# untitled.net
KiCad netlist of a schematic drawn in EAGLE
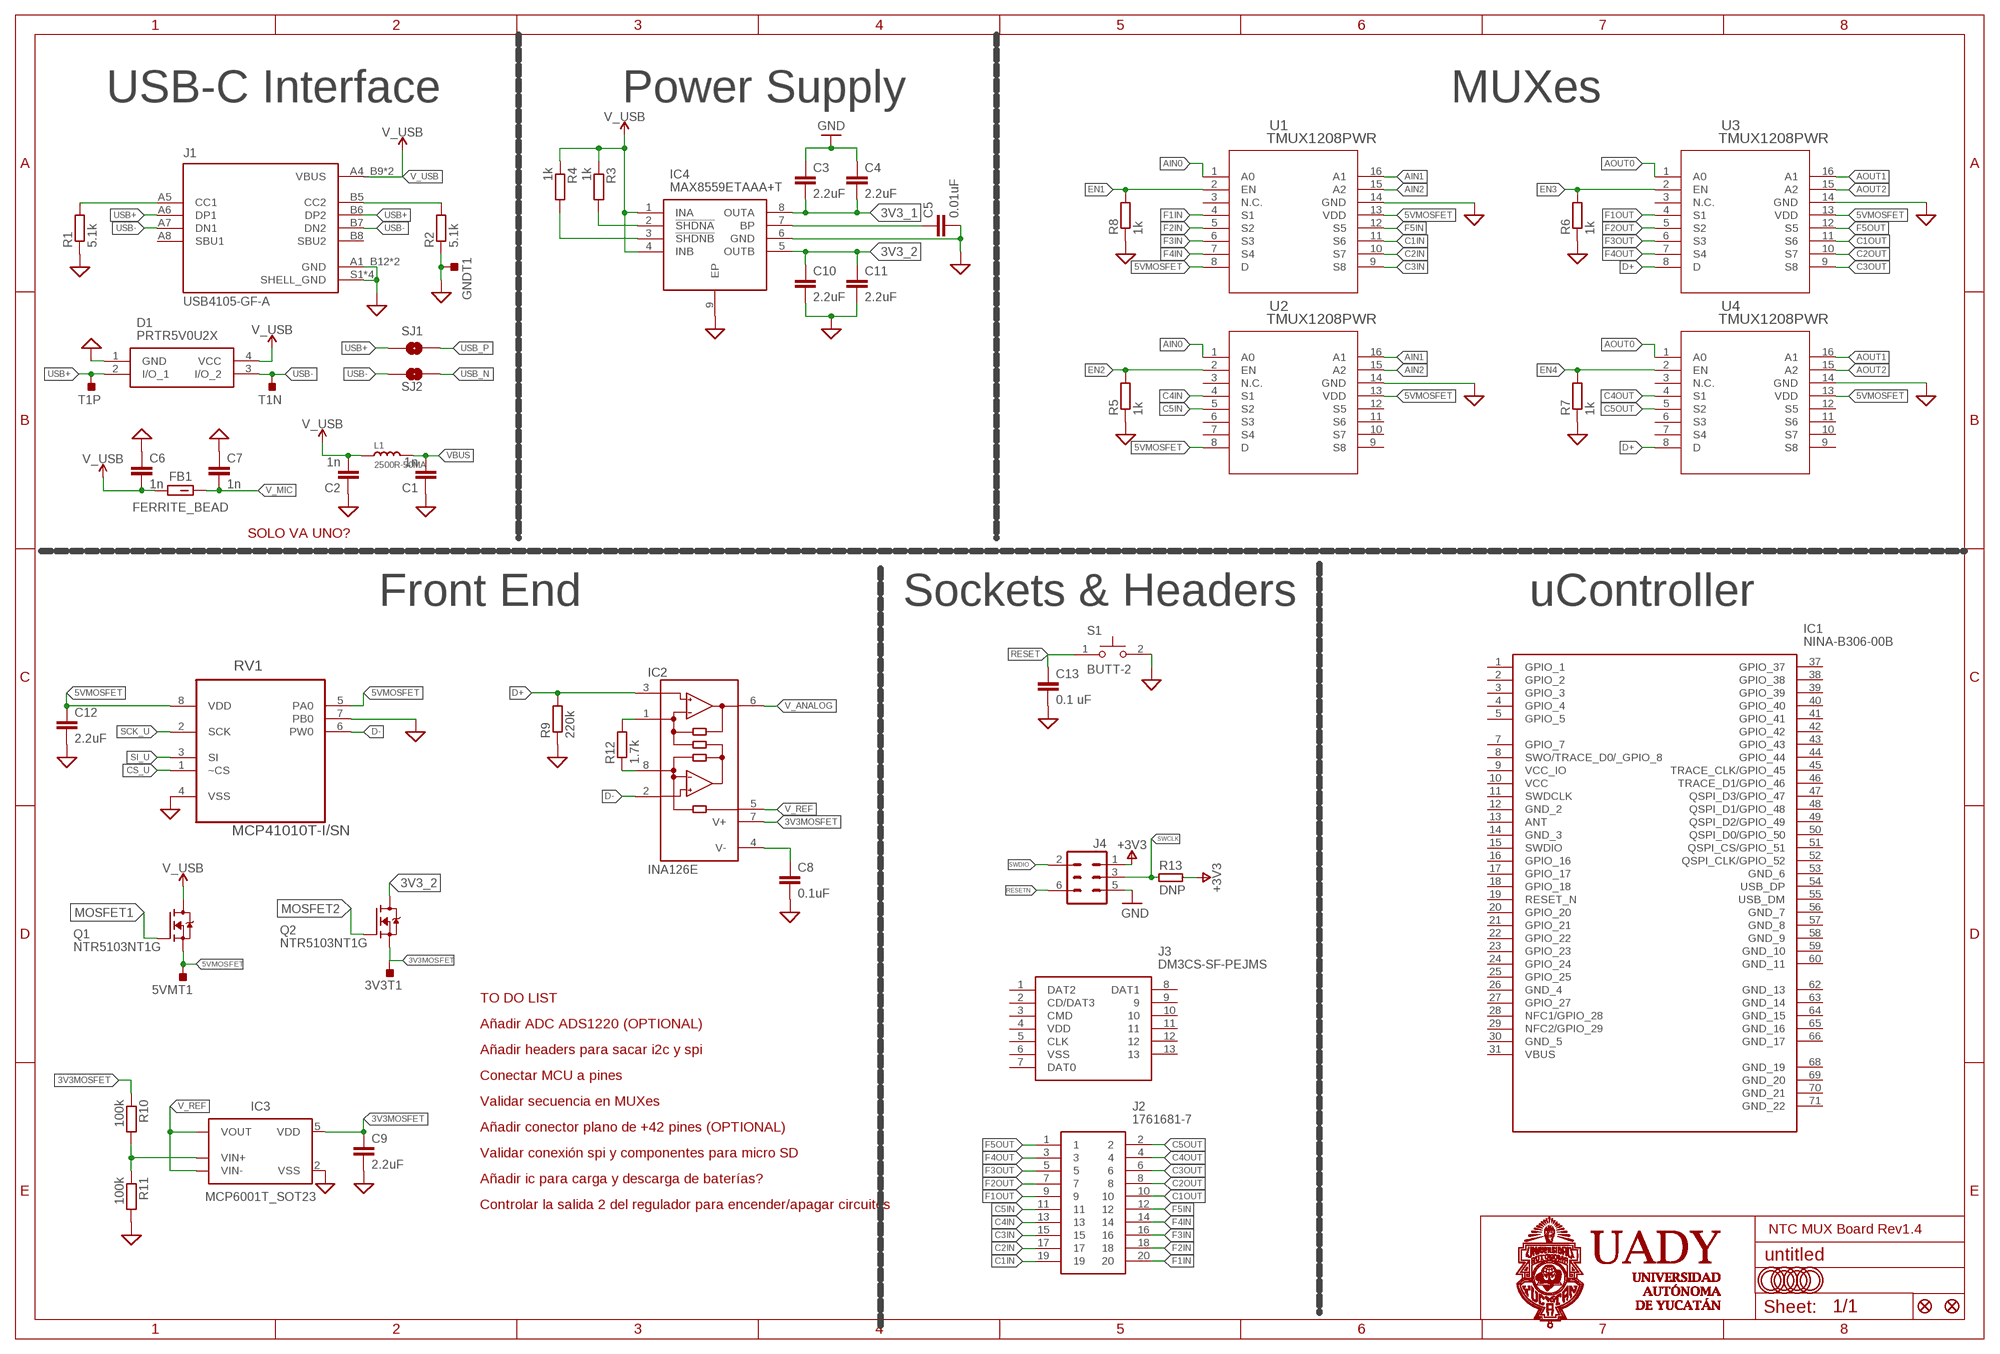
[diagram p0: schematic, sheet 1]

(export (version "E")
  (design (tool "Eeschema 10.0.6"))
  (components
    (comp (ref "3V3T1")
      (value "TESTPOINT_TPS-SMD-10SN")
      (footprint "eagle-import:TESTPOINT_SMD-10SN")
      (libsource (lib "eagle-import") (part "TESTPOINT_TPS-SMD-10SN"))
    )
    (comp (ref "5VMT1")
      (value "TESTPOINT_TPS-SMD-10SN")
      (footprint "eagle-import:TESTPOINT_SMD-10SN")
      (libsource (lib "eagle-import") (part "TESTPOINT_TPS-SMD-10SN"))
    )
    (comp (ref "C1")
      (value "1n")
      (footprint "eagle-import:C0603")
      (libsource (lib "eagle-import") (part "C-EUC0603"))
    )
    (comp (ref "C2")
      (value "1n")
      (footprint "eagle-import:C0603")
      (libsource (lib "eagle-import") (part "C-EUC0603"))
    )
    (comp (ref "C3")
      (value "2.2uF")
      (footprint "eagle-import:C0603")
      (libsource (lib "eagle-import") (part "C-EUC0603"))
    )
    (comp (ref "C4")
      (value "2.2uF")
      (footprint "eagle-import:C0603")
      (libsource (lib "eagle-import") (part "C-EUC0603"))
    )
    (comp (ref "C5")
      (value "0.01uF")
      (footprint "eagle-import:C0603")
      (libsource (lib "eagle-import") (part "C-EUC0603"))
    )
    (comp (ref "C6")
      (value "1n")
      (footprint "eagle-import:C0603")
      (libsource (lib "eagle-import") (part "C-EUC0603"))
    )
    (comp (ref "C7")
      (value "1n")
      (footprint "eagle-import:C0603")
      (libsource (lib "eagle-import") (part "C-EUC0603"))
    )
    (comp (ref "C8")
      (value "0.1uF")
      (footprint "eagle-import:C0603")
      (libsource (lib "eagle-import") (part "C-EUC0603"))
    )
    (comp (ref "C9")
      (value "2.2uF")
      (footprint "eagle-import:C0603")
      (libsource (lib "eagle-import") (part "C-EUC0603"))
    )
    (comp (ref "C10")
      (value "2.2uF")
      (footprint "eagle-import:C0603")
      (libsource (lib "eagle-import") (part "C-EUC0603"))
    )
    (comp (ref "C11")
      (value "2.2uF")
      (footprint "eagle-import:C0603")
      (libsource (lib "eagle-import") (part "C-EUC0603"))
    )
    (comp (ref "C12")
      (value "2.2uF")
      (footprint "eagle-import:C0603")
      (libsource (lib "eagle-import") (part "C-EUC0603"))
    )
    (comp (ref "C13")
      (value "0.1 uF")
      (footprint "eagle-import:C0603")
      (libsource (lib "eagle-import") (part "C-EUC0603"))
    )
    (comp (ref "D1")
      (value "PRTR5V0U2X")
      (footprint "eagle-import:PRTR5V0U2X")
      (libsource (lib "eagle-import") (part "PRTR5V0U2X"))
    )
    (comp (ref "FB1")
      (value "FERRITE_BEAD")
      (footprint "eagle-import:BEADC1608X95N")
      (libsource (lib "eagle-import") (part "FBCHIP-0603(1608-METRIC)"))
    )
    (comp (ref "FID1")
      (value "FIDUCIAL_1MM")
      (footprint "eagle-import:FIDUCIAL_1MM")
      (libsource (lib "eagle-import") (part "FIDUCIAL_1MM"))
    )
    (comp (ref "FID4")
      (value "FIDUCIAL_1MM")
      (footprint "eagle-import:FIDUCIAL_1MM")
      (libsource (lib "eagle-import") (part "FIDUCIAL_1MM"))
    )
    (comp (ref "GNDT1")
      (value "TESTPOINT_TPS-SMD-10SN")
      (footprint "eagle-import:TESTPOINT_SMD-10SN")
      (libsource (lib "eagle-import") (part "TESTPOINT_TPS-SMD-10SN"))
    )
    (comp (ref "IC1")
      (value "NINA-B306-00B")
      (footprint "eagle-import:NINAB30600B")
      (fields (field (name "MOUSER_PART_NUMBER") "377-NINA-B306-00B"))
      (libsource (lib "eagle-import") (part "NINA-B306-00B"))
    )
    (comp (ref "IC2")
      (value "INA126E")
      (footprint "eagle-import:MSOP08")
      (fields (field (name "MF") "Texas Instruments") (field (name "MP") "INA126"))
      (libsource (lib "eagle-import") (part "INA126E"))
    )
    (comp (ref "IC3")
      (value "MCP6001T_SOT23")
      (footprint "eagle-import:SOT95P280X145-5N")
      (fields (field (name "MANUFACTURER") "Microchip Technology") (field (name "MPN") "Generic"))
      (libsource (lib "eagle-import") (part "MCP6001T_SOT23"))
    )
    (comp (ref "IC4")
      (value "MAX8559ETAAA+T")
      (footprint "eagle-import:SON65P300X300X80-9N")
      (fields (field (name "MOUSER_PART_NUMBER") "700-MAX8559ETAAAT"))
      (libsource (lib "eagle-import") (part "MAX8559ETAAA+T"))
    )
    (comp (ref "J1")
      (value "USB4105-GF-A")
      (footprint "eagle-import:GCT_USB4105-GF-A")
      (fields (field (name "MF") "GCT"))
      (libsource (lib "eagle-import") (part "USB4105-GF-A"))
    )
    (comp (ref "J2")
      (value "1761681-7")
      (footprint "eagle-import:SHDR20W66P254_2X10_3302X883X92")
      (fields (field (name "MOUSER_PART_NUMBER") "571-1761681-7"))
      (libsource (lib "eagle-import") (part "1761681-7"))
    )
    (comp (ref "J3")
      (value "DM3CS-SF-PEJMS")
      (footprint "eagle-import:DM3CSSFPEJMS")
      (libsource (lib "eagle-import") (part "DM3CS-SF-PEJMS"))
    )
    (comp (ref "J4")
      (value "DNP")
      (footprint "eagle-import:2X03-TP1")
      (libsource (lib "eagle-import") (part "PINHD-2X03(NO4)"))
    )
    (comp (ref "L1")
      (value "2500R-50MA")
      (footprint "eagle-import:L0603")
      (libsource (lib "eagle-import") (part "SMD-FERRITE-BEAD-2500R-50MA(0603)"))
    )
    (comp (ref "Q1")
      (value "NTR5103NT1G")
      (footprint "eagle-import:SOT95P237X111-3N")
      (fields (field (name "MF") "ON Semiconductor"))
      (libsource (lib "eagle-import") (part "NTR5103NT1G"))
    )
    (comp (ref "Q2")
      (value "NTR5103NT1G")
      (footprint "eagle-import:SOT95P237X111-3N")
      (fields (field (name "MF") "ON Semiconductor"))
      (libsource (lib "eagle-import") (part "NTR5103NT1G"))
    )
    (comp (ref "R1")
      (value "5.1k")
      (footprint "eagle-import:R0603")
      (libsource (lib "eagle-import") (part "R-EU_R0603"))
    )
    (comp (ref "R2")
      (value "5.1k")
      (footprint "eagle-import:R0603")
      (libsource (lib "eagle-import") (part "R-EU_R0603"))
    )
    (comp (ref "R3")
      (value "1k")
      (footprint "eagle-import:R0603")
      (libsource (lib "eagle-import") (part "R-EU_R0603"))
    )
    (comp (ref "R4")
      (value "1k")
      (footprint "eagle-import:R0603")
      (libsource (lib "eagle-import") (part "R-EU_R0603"))
    )
    (comp (ref "R5")
      (value "1k")
      (footprint "eagle-import:R0603")
      (libsource (lib "eagle-import") (part "R-EU_R0603"))
    )
    (comp (ref "R6")
      (value "1k")
      (footprint "eagle-import:R0603")
      (libsource (lib "eagle-import") (part "R-EU_R0603"))
    )
    (comp (ref "R7")
      (value "1k")
      (footprint "eagle-import:R0603")
      (libsource (lib "eagle-import") (part "R-EU_R0603"))
    )
    (comp (ref "R8")
      (value "1k")
      (footprint "eagle-import:R0603")
      (libsource (lib "eagle-import") (part "R-EU_R0603"))
    )
    (comp (ref "R9")
      (value "220k")
      (footprint "eagle-import:R0603")
      (libsource (lib "eagle-import") (part "R-EU_R0603"))
    )
    (comp (ref "R10")
      (value "100k")
      (footprint "eagle-import:R0603")
      (libsource (lib "eagle-import") (part "R-EU_R0603"))
    )
    (comp (ref "R11")
      (value "100k")
      (footprint "eagle-import:R0603")
      (libsource (lib "eagle-import") (part "R-EU_R0603"))
    )
    (comp (ref "R12")
      (value "1.7k")
      (footprint "eagle-import:R0603")
      (libsource (lib "eagle-import") (part "R-EU_R0603"))
    )
    (comp (ref "R13")
      (value "DNP")
      (footprint "eagle-import:0402-1005X55N")
      (libsource (lib "eagle-import") (part "R-0402-DNP"))
    )
    (comp (ref "RV1")
      (value "MCP41010T-I/SN")
      (footprint "eagle-import:SOIC127P600X175-8N")
      (fields (field (name "MF") "Microchip Technology"))
      (libsource (lib "eagle-import") (part "MCP41010T-I/SN"))
    )
    (comp (ref "S1")
      (value "BUTT-2")
      (footprint "eagle-import:SW_BUTT-2")
      (fields (field (name "MF") "Gravitech"))
      (libsource (lib "eagle-import") (part "BUTT-2"))
    )
    (comp (ref "SJ1")
      (value "JUMPER-SMT_2_NO_NO-SILK")
      (footprint "eagle-import:SMT-JUMPER_2_NO_NO-SILK")
      (libsource (lib "eagle-import") (part "JUMPER-SMT_2_NO_NO-SILK"))
    )
    (comp (ref "SJ2")
      (value "JUMPER-SMT_2_NO_NO-SILK")
      (footprint "eagle-import:SMT-JUMPER_2_NO_NO-SILK")
      (libsource (lib "eagle-import") (part "JUMPER-SMT_2_NO_NO-SILK"))
    )
    (comp (ref "T1N")
      (value "TESTPOINT_TPS-SMD-10SN")
      (footprint "eagle-import:TESTPOINT_SMD-10SN")
      (libsource (lib "eagle-import") (part "TESTPOINT_TPS-SMD-10SN"))
    )
    (comp (ref "T1P")
      (value "TESTPOINT_TPS-SMD-10SN")
      (footprint "eagle-import:TESTPOINT_SMD-10SN")
      (libsource (lib "eagle-import") (part "TESTPOINT_TPS-SMD-10SN"))
    )
    (comp (ref "U$2")
      (value "MOUNTINGHOLE2.5")
      (footprint "eagle-import:MOUNTINGHOLE_2.5_PLATED")
      (libsource (lib "eagle-import") (part "MOUNTINGHOLE2.5"))
    )
    (comp (ref "U$3")
      (value "MOUNTINGHOLE2.5")
      (footprint "eagle-import:MOUNTINGHOLE_2.5_PLATED")
      (libsource (lib "eagle-import") (part "MOUNTINGHOLE2.5"))
    )
    (comp (ref "U$4")
      (value "MOUNTINGHOLE2.5")
      (footprint "eagle-import:MOUNTINGHOLE_2.5_PLATED")
      (libsource (lib "eagle-import") (part "MOUNTINGHOLE2.5"))
    )
    (comp (ref "U$24")
      (value "MOUNTINGHOLE2.5")
      (footprint "eagle-import:MOUNTINGHOLE_2.5_PLATED")
      (libsource (lib "eagle-import") (part "MOUNTINGHOLE2.5"))
    )
    (comp (ref "U1")
      (value "TMUX1208PWR")
      (footprint "eagle-import:PW_16_TEX")
      (fields (field (name "COPYRIGHT") "Copyright (C) 2022 Ultra Librarian. All rights reserved."))
      (libsource (lib "eagle-import") (part "TMUX1208PWR"))
    )
    (comp (ref "U2")
      (value "TMUX1208PWR")
      (footprint "eagle-import:PW_16_TEX")
      (fields (field (name "COPYRIGHT") "Copyright (C) 2022 Ultra Librarian. All rights reserved."))
      (libsource (lib "eagle-import") (part "TMUX1208PWR"))
    )
    (comp (ref "U3")
      (value "TMUX1208PWR")
      (footprint "eagle-import:PW_16_TEX")
      (fields (field (name "COPYRIGHT") "Copyright (C) 2022 Ultra Librarian. All rights reserved."))
      (libsource (lib "eagle-import") (part "TMUX1208PWR"))
    )
    (comp (ref "U4")
      (value "TMUX1208PWR")
      (footprint "eagle-import:PW_16_TEX")
      (fields (field (name "COPYRIGHT") "Copyright (C) 2022 Ultra Librarian. All rights reserved."))
      (libsource (lib "eagle-import") (part "TMUX1208PWR"))
    )
  )
  (nets
    (net (code "1") (name "+3V3") (class "Default")
      (node (ref "J4") (pin "1") (pinfunction "1_1") (pintype "passive"))
      (node (ref "R13") (pin "1") (pinfunction "1_1") (pintype "passive"))
    )
    (net (code "2") (name "3V3MOSFET") (class "Default")
      (node (ref "3V3T1") (pin "TP") (pinfunction "TP_TP") (pintype "passive"))
      (node (ref "C9") (pin "1") (pinfunction "1_1") (pintype "passive"))
      (node (ref "IC2") (pin "7") (pinfunction "V+_7") (pintype "power_in"))
      (node (ref "IC3") (pin "5") (pinfunction "VDD_5") (pintype "bidirectional"))
      (node (ref "Q2") (pin "2") (pinfunction "S_2") (pintype "passive"))
      (node (ref "R10") (pin "1") (pinfunction "1_1") (pintype "passive"))
    )
    (net (code "3") (name "3V3_1") (class "Default")
      (node (ref "C3") (pin "2") (pinfunction "2_2") (pintype "passive"))
      (node (ref "C4") (pin "2") (pinfunction "2_2") (pintype "passive"))
      (node (ref "IC4") (pin "8") (pinfunction "OUTA_8") (pintype "bidirectional"))
    )
    (net (code "4") (name "3V3_2") (class "Default")
      (node (ref "C10") (pin "1") (pinfunction "1_1") (pintype "passive"))
      (node (ref "C11") (pin "1") (pinfunction "1_1") (pintype "passive"))
      (node (ref "IC4") (pin "5") (pinfunction "OUTB_5") (pintype "bidirectional"))
      (node (ref "Q2") (pin "3") (pinfunction "D_3") (pintype "passive"))
    )
    (net (code "5") (name "5VMOSFET") (class "Default")
      (node (ref "5VMT1") (pin "TP") (pinfunction "TP_TP") (pintype "passive"))
      (node (ref "C12") (pin "1") (pinfunction "1_1") (pintype "passive"))
      (node (ref "Q1") (pin "2") (pinfunction "S_2") (pintype "passive"))
      (node (ref "RV1") (pin "5") (pinfunction "PA0_5") (pintype "bidirectional"))
      (node (ref "RV1") (pin "8") (pinfunction "VDD_8") (pintype "power_in"))
      (node (ref "U1") (pin "13") (pinfunction "VDD_13") (pintype "power_in"))
      (node (ref "U1") (pin "8") (pinfunction "D_8") (pintype "passive"))
      (node (ref "U2") (pin "13") (pinfunction "VDD_13") (pintype "power_in"))
      (node (ref "U2") (pin "8") (pinfunction "D_8") (pintype "passive"))
      (node (ref "U3") (pin "13") (pinfunction "VDD_13") (pintype "power_in"))
      (node (ref "U4") (pin "13") (pinfunction "VDD_13") (pintype "power_in"))
    )
    (net (code "6") (name "AIN0") (class "Default")
      (node (ref "U1") (pin "1") (pinfunction "A0_1") (pintype "bidirectional"))
      (node (ref "U2") (pin "1") (pinfunction "A0_1") (pintype "bidirectional"))
    )
    (net (code "7") (name "AIN1") (class "Default")
      (node (ref "U1") (pin "16") (pinfunction "A1_16") (pintype "bidirectional"))
      (node (ref "U2") (pin "16") (pinfunction "A1_16") (pintype "bidirectional"))
    )
    (net (code "8") (name "AIN2") (class "Default")
      (node (ref "U1") (pin "15") (pinfunction "A2_15") (pintype "bidirectional"))
      (node (ref "U2") (pin "15") (pinfunction "A2_15") (pintype "bidirectional"))
    )
    (net (code "9") (name "AOUT0") (class "Default")
      (node (ref "U3") (pin "1") (pinfunction "A0_1") (pintype "bidirectional"))
      (node (ref "U4") (pin "1") (pinfunction "A0_1") (pintype "bidirectional"))
    )
    (net (code "10") (name "AOUT1") (class "Default")
      (node (ref "U3") (pin "16") (pinfunction "A1_16") (pintype "bidirectional"))
      (node (ref "U4") (pin "16") (pinfunction "A1_16") (pintype "bidirectional"))
    )
    (net (code "11") (name "AOUT2") (class "Default")
      (node (ref "U3") (pin "15") (pinfunction "A2_15") (pintype "bidirectional"))
      (node (ref "U4") (pin "15") (pinfunction "A2_15") (pintype "bidirectional"))
    )
    (net (code "12") (name "C1IN") (class "Default")
      (node (ref "J2") (pin "19") (pinfunction "19_19") (pintype "bidirectional"))
      (node (ref "U1") (pin "11") (pinfunction "S6_11") (pintype "bidirectional"))
    )
    (net (code "13") (name "C1OUT") (class "Default")
      (node (ref "J2") (pin "10") (pinfunction "10_10") (pintype "bidirectional"))
      (node (ref "U3") (pin "11") (pinfunction "S6_11") (pintype "bidirectional"))
    )
    (net (code "14") (name "C2IN") (class "Default")
      (node (ref "J2") (pin "17") (pinfunction "17_17") (pintype "bidirectional"))
      (node (ref "U1") (pin "10") (pinfunction "S7_10") (pintype "bidirectional"))
    )
    (net (code "15") (name "C2OUT") (class "Default")
      (node (ref "J2") (pin "8") (pinfunction "8_8") (pintype "bidirectional"))
      (node (ref "U3") (pin "10") (pinfunction "S7_10") (pintype "bidirectional"))
    )
    (net (code "16") (name "C3IN") (class "Default")
      (node (ref "J2") (pin "15") (pinfunction "15_15") (pintype "bidirectional"))
      (node (ref "U1") (pin "9") (pinfunction "S8_9") (pintype "bidirectional"))
    )
    (net (code "17") (name "C3OUT") (class "Default")
      (node (ref "J2") (pin "6") (pinfunction "6_6") (pintype "bidirectional"))
      (node (ref "U3") (pin "9") (pinfunction "S8_9") (pintype "bidirectional"))
    )
    (net (code "18") (name "C4IN") (class "Default")
      (node (ref "J2") (pin "13") (pinfunction "13_13") (pintype "bidirectional"))
      (node (ref "U2") (pin "4") (pinfunction "S1_4") (pintype "bidirectional"))
    )
    (net (code "19") (name "C4OUT") (class "Default")
      (node (ref "J2") (pin "4") (pinfunction "4_4") (pintype "bidirectional"))
      (node (ref "U4") (pin "4") (pinfunction "S1_4") (pintype "bidirectional"))
    )
    (net (code "20") (name "C5IN") (class "Default")
      (node (ref "J2") (pin "11") (pinfunction "11_11") (pintype "bidirectional"))
      (node (ref "U2") (pin "5") (pinfunction "S2_5") (pintype "bidirectional"))
    )
    (net (code "21") (name "C5OUT") (class "Default")
      (node (ref "J2") (pin "2") (pinfunction "2_2") (pintype "bidirectional"))
      (node (ref "U4") (pin "5") (pinfunction "S2_5") (pintype "bidirectional"))
    )
    (net (code "22") (name "CS_U") (class "Default")
      (node (ref "RV1") (pin "1") (pinfunction "~{CS}_1") (pintype "input"))
    )
    (net (code "23") (name "D+") (class "Default")
      (node (ref "IC2") (pin "3") (pinfunction "+IN_3") (pintype "input"))
      (node (ref "R9") (pin "2") (pinfunction "2_2") (pintype "passive"))
      (node (ref "U3") (pin "8") (pinfunction "D_8") (pintype "passive"))
      (node (ref "U4") (pin "8") (pinfunction "D_8") (pintype "passive"))
    )
    (net (code "24") (name "D-") (class "Default")
      (node (ref "IC2") (pin "2") (pinfunction "-IN_2") (pintype "input"))
      (node (ref "RV1") (pin "6") (pinfunction "PW0_6") (pintype "bidirectional"))
    )
    (net (code "25") (name "EN1") (class "Default")
      (node (ref "R8") (pin "2") (pinfunction "2_2") (pintype "passive"))
      (node (ref "U1") (pin "2") (pinfunction "EN_2") (pintype "passive"))
    )
    (net (code "26") (name "EN2") (class "Default")
      (node (ref "R5") (pin "2") (pinfunction "2_2") (pintype "passive"))
      (node (ref "U2") (pin "2") (pinfunction "EN_2") (pintype "passive"))
    )
    (net (code "27") (name "EN3") (class "Default")
      (node (ref "R6") (pin "2") (pinfunction "2_2") (pintype "passive"))
      (node (ref "U3") (pin "2") (pinfunction "EN_2") (pintype "passive"))
    )
    (net (code "28") (name "EN4") (class "Default")
      (node (ref "R7") (pin "2") (pinfunction "2_2") (pintype "passive"))
      (node (ref "U4") (pin "2") (pinfunction "EN_2") (pintype "passive"))
    )
    (net (code "29") (name "F1IN") (class "Default")
      (node (ref "J2") (pin "20") (pinfunction "20_20") (pintype "bidirectional"))
      (node (ref "U1") (pin "4") (pinfunction "S1_4") (pintype "bidirectional"))
    )
    (net (code "30") (name "F1OUT") (class "Default")
      (node (ref "J2") (pin "9") (pinfunction "9_9") (pintype "bidirectional"))
      (node (ref "U3") (pin "4") (pinfunction "S1_4") (pintype "bidirectional"))
    )
    (net (code "31") (name "F2IN") (class "Default")
      (node (ref "J2") (pin "18") (pinfunction "18_18") (pintype "bidirectional"))
      (node (ref "U1") (pin "5") (pinfunction "S2_5") (pintype "bidirectional"))
    )
    (net (code "32") (name "F2OUT") (class "Default")
      (node (ref "J2") (pin "7") (pinfunction "7_7") (pintype "bidirectional"))
      (node (ref "U3") (pin "5") (pinfunction "S2_5") (pintype "bidirectional"))
    )
    (net (code "33") (name "F3IN") (class "Default")
      (node (ref "J2") (pin "16") (pinfunction "16_16") (pintype "bidirectional"))
      (node (ref "U1") (pin "6") (pinfunction "S3_6") (pintype "bidirectional"))
    )
    (net (code "34") (name "F3OUT") (class "Default")
      (node (ref "J2") (pin "5") (pinfunction "5_5") (pintype "bidirectional"))
      (node (ref "U3") (pin "6") (pinfunction "S3_6") (pintype "bidirectional"))
    )
    (net (code "35") (name "F4IN") (class "Default")
      (node (ref "J2") (pin "14") (pinfunction "14_14") (pintype "bidirectional"))
      (node (ref "U1") (pin "7") (pinfunction "S4_7") (pintype "bidirectional"))
    )
    (net (code "36") (name "F4OUT") (class "Default")
      (node (ref "J2") (pin "3") (pinfunction "3_3") (pintype "bidirectional"))
      (node (ref "U3") (pin "7") (pinfunction "S4_7") (pintype "bidirectional"))
    )
    (net (code "37") (name "F5IN") (class "Default")
      (node (ref "J2") (pin "12") (pinfunction "12_12") (pintype "bidirectional"))
      (node (ref "U1") (pin "12") (pinfunction "S5_12") (pintype "bidirectional"))
    )
    (net (code "38") (name "F5OUT") (class "Default")
      (node (ref "J2") (pin "1") (pinfunction "1_1") (pintype "bidirectional"))
      (node (ref "U3") (pin "12") (pinfunction "S5_12") (pintype "bidirectional"))
    )
    (net (code "39") (name "GND") (class "Default")
      (node (ref "C1") (pin "1") (pinfunction "1_1") (pintype "passive"))
      (node (ref "C10") (pin "2") (pinfunction "2_2") (pintype "passive"))
      (node (ref "C11") (pin "2") (pinfunction "2_2") (pintype "passive"))
      (node (ref "C12") (pin "2") (pinfunction "2_2") (pintype "passive"))
      (node (ref "C13") (pin "2") (pinfunction "2_2") (pintype "passive"))
      (node (ref "C2") (pin "1") (pinfunction "1_1") (pintype "passive"))
      (node (ref "C3") (pin "1") (pinfunction "1_1") (pintype "passive"))
      (node (ref "C4") (pin "1") (pinfunction "1_1") (pintype "passive"))
      (node (ref "C5") (pin "2") (pinfunction "2_2") (pintype "passive"))
      (node (ref "C6") (pin "1") (pinfunction "1_1") (pintype "passive"))
      (node (ref "C7") (pin "1") (pinfunction "1_1") (pintype "passive"))
      (node (ref "C8") (pin "2") (pinfunction "2_2") (pintype "passive"))
      (node (ref "C9") (pin "2") (pinfunction "2_2") (pintype "passive"))
      (node (ref "D1") (pin "1") (pinfunction "GND_1") (pintype "bidirectional"))
      (node (ref "GNDT1") (pin "TP") (pinfunction "TP_TP") (pintype "passive"))
      (node (ref "IC3") (pin "2") (pinfunction "VSS_2") (pintype "bidirectional"))
      (node (ref "IC4") (pin "6") (pinfunction "GND_6") (pintype "bidirectional"))
      (node (ref "IC4") (pin "9") (pinfunction "EP_9") (pintype "bidirectional"))
      (node (ref "J1") (pin "A1_B12") (pinfunction "GND_A1_B12") (pintype "power_in"))
      (node (ref "J1") (pin "B1_A12") (pinfunction "GND_B1_A12") (pintype "power_in"))
      (node (ref "J1") (pin "S1") (pinfunction "SHELL_GND_S1") (pintype "power_in"))
      (node (ref "J1") (pin "S2") (pinfunction "SHELL_GND_S2") (pintype "power_in"))
      (node (ref "J1") (pin "S3") (pinfunction "SHELL_GND_S3") (pintype "power_in"))
      (node (ref "J1") (pin "S4") (pinfunction "SHELL_GND_S4") (pintype "power_in"))
      (node (ref "J4") (pin "5") (pinfunction "5_5") (pintype "passive"))
      (node (ref "R1") (pin "1") (pinfunction "1_1") (pintype "passive"))
      (node (ref "R11") (pin "2") (pinfunction "2_2") (pintype "passive"))
      (node (ref "R2") (pin "1") (pinfunction "1_1") (pintype "passive"))
      (node (ref "R5") (pin "1") (pinfunction "1_1") (pintype "passive"))
      (node (ref "R6") (pin "1") (pinfunction "1_1") (pintype "passive"))
      (node (ref "R7") (pin "1") (pinfunction "1_1") (pintype "passive"))
      (node (ref "R8") (pin "1") (pinfunction "1_1") (pintype "passive"))
      (node (ref "R9") (pin "1") (pinfunction "1_1") (pintype "passive"))
      (node (ref "RV1") (pin "4") (pinfunction "VSS_4") (pintype "passive"))
      (node (ref "RV1") (pin "7") (pinfunction "PB0_7") (pintype "bidirectional"))
      (node (ref "S1") (pin "2") (pinfunction "2_2") (pintype "passive"))
      (node (ref "U1") (pin "14") (pinfunction "GND_14") (pintype "passive"))
      (node (ref "U2") (pin "14") (pinfunction "GND_14") (pintype "passive"))
      (node (ref "U3") (pin "14") (pinfunction "GND_14") (pintype "passive"))
      (node (ref "U4") (pin "14") (pinfunction "GND_14") (pintype "passive"))
    )
    (net (code "40") (name "MOSFET1") (class "Default")
      (node (ref "Q1") (pin "1") (pinfunction "G_1") (pintype "passive"))
    )
    (net (code "41") (name "MOSFET2") (class "Default")
      (node (ref "Q2") (pin "1") (pinfunction "G_1") (pintype "passive"))
    )
    (net (code "42") (name "Net-(IC2-RG-Pad1)") (class "Default")
      (node (ref "IC2") (pin "1") (pinfunction "RG_1") (pintype "passive"))
      (node (ref "R12") (pin "2") (pinfunction "2_2") (pintype "passive"))
    )
    (net (code "43") (name "Net-(IC2-RG-Pad8)") (class "Default")
      (node (ref "IC2") (pin "8") (pinfunction "RG_8") (pintype "passive"))
      (node (ref "R12") (pin "1") (pinfunction "1_1") (pintype "passive"))
    )
    (net (code "44") (name "Net-(IC2-V-)") (class "Default")
      (node (ref "C8") (pin "1") (pinfunction "1_1") (pintype "passive"))
      (node (ref "IC2") (pin "4") (pinfunction "V-_4") (pintype "power_in"))
    )
    (net (code "45") (name "Net-(IC3-VIN+)") (class "Default")
      (node (ref "IC3") (pin "3") (pinfunction "VIN+_3") (pintype "input"))
      (node (ref "R10") (pin "2") (pinfunction "2_2") (pintype "passive"))
      (node (ref "R11") (pin "1") (pinfunction "1_1") (pintype "passive"))
    )
    (net (code "46") (name "Net-(IC4-BP)") (class "Default")
      (node (ref "C5") (pin "1") (pinfunction "1_1") (pintype "passive"))
      (node (ref "IC4") (pin "7") (pinfunction "BP_7") (pintype "bidirectional"))
    )
    (net (code "47") (name "Net-(IC4-~{SHDNA})") (class "Default")
      (node (ref "IC4") (pin "2") (pinfunction "~{SHDNA}_2") (pintype "bidirectional"))
      (node (ref "R3") (pin "2") (pinfunction "2_2") (pintype "passive"))
    )
    (net (code "48") (name "Net-(IC4-~{SHDNB})") (class "Default")
      (node (ref "IC4") (pin "3") (pinfunction "~{SHDNB}_3") (pintype "bidirectional"))
      (node (ref "R4") (pin "2") (pinfunction "2_2") (pintype "passive"))
    )
    (net (code "49") (name "Net-(J1-CC1)") (class "Default")
      (node (ref "J1") (pin "A5") (pinfunction "CC1_A5") (pintype "bidirectional"))
      (node (ref "R1") (pin "2") (pinfunction "2_2") (pintype "passive"))
    )
    (net (code "50") (name "Net-(J1-CC2)") (class "Default")
      (node (ref "J1") (pin "B5") (pinfunction "CC2_B5") (pintype "bidirectional"))
      (node (ref "R2") (pin "2") (pinfunction "2_2") (pintype "passive"))
    )
    (net (code "51") (name "RESET") (class "Default")
      (node (ref "C13") (pin "1") (pinfunction "1_1") (pintype "passive"))
      (node (ref "S1") (pin "1") (pinfunction "1_1") (pintype "passive"))
    )
    (net (code "52") (name "RESETN") (class "Default")
      (node (ref "J4") (pin "6") (pinfunction "6_6") (pintype "passive"))
    )
    (net (code "53") (name "SCK_U") (class "Default")
      (node (ref "RV1") (pin "2") (pinfunction "SCK_2") (pintype "input"))
    )
    (net (code "54") (name "SI_U") (class "Default")
      (node (ref "RV1") (pin "3") (pinfunction "SI_3") (pintype "input"))
    )
    (net (code "55") (name "SWCLK") (class "Default")
      (node (ref "J4") (pin "3") (pinfunction "3_3") (pintype "passive"))
      (node (ref "R13") (pin "2") (pinfunction "2_2") (pintype "passive"))
    )
    (net (code "56") (name "SWDIO") (class "Default")
      (node (ref "J4") (pin "2") (pinfunction "2_2") (pintype "passive"))
    )
    (net (code "57") (name "USB+") (class "Default")
      (node (ref "D1") (pin "2") (pinfunction "I/O_1_2") (pintype "bidirectional"))
      (node (ref "J1") (pin "A6") (pinfunction "DP1_A6") (pintype "bidirectional"))
      (node (ref "J1") (pin "B6") (pinfunction "DP2_B6") (pintype "bidirectional"))
      (node (ref "SJ1") (pin "1") (pinfunction "1_1") (pintype "passive"))
      (node (ref "T1P") (pin "TP") (pinfunction "TP_TP") (pintype "passive"))
    )
    (net (code "58") (name "USB-") (class "Default")
      (node (ref "D1") (pin "3") (pinfunction "I/O_2_3") (pintype "bidirectional"))
      (node (ref "J1") (pin "A7") (pinfunction "DN1_A7") (pintype "bidirectional"))
      (node (ref "J1") (pin "B7") (pinfunction "DN2_B7") (pintype "bidirectional"))
      (node (ref "SJ2") (pin "1") (pinfunction "1_1") (pintype "passive"))
      (node (ref "T1N") (pin "TP") (pinfunction "TP_TP") (pintype "passive"))
    )
    (net (code "59") (name "USB_N") (class "Default")
      (node (ref "SJ2") (pin "2") (pinfunction "2_2") (pintype "passive"))
    )
    (net (code "60") (name "USB_P") (class "Default")
      (node (ref "SJ1") (pin "2") (pinfunction "2_2") (pintype "passive"))
    )
    (net (code "61") (name "VBUS") (class "Default")
      (node (ref "C1") (pin "2") (pinfunction "2_2") (pintype "passive"))
      (node (ref "L1") (pin "2") (pinfunction "2_2") (pintype "passive"))
    )
    (net (code "62") (name "V_ANALOG") (class "Default")
      (node (ref "IC2") (pin "6") (pinfunction "OUT_6") (pintype "output"))
    )
    (net (code "63") (name "V_MIC") (class "Default")
      (node (ref "C7") (pin "2") (pinfunction "2_2") (pintype "passive"))
      (node (ref "FB1") (pin "2") (pinfunction "2_2") (pintype "passive"))
    )
    (net (code "64") (name "V_REF") (class "Default")
      (node (ref "IC2") (pin "5") (pinfunction "REF_5") (pintype "passive"))
      (node (ref "IC3") (pin "1") (pinfunction "VOUT_1") (pintype "output"))
      (node (ref "IC3") (pin "4") (pinfunction "VIN-_4") (pintype "input"))
    )
    (net (code "65") (name "V_USB") (class "Default")
      (node (ref "C2") (pin "2") (pinfunction "2_2") (pintype "passive"))
      (node (ref "C6") (pin "2") (pinfunction "2_2") (pintype "passive"))
      (node (ref "D1") (pin "4") (pinfunction "VCC_4") (pintype "bidirectional"))
      (node (ref "FB1") (pin "1") (pinfunction "1_1") (pintype "passive"))
      (node (ref "IC4") (pin "1") (pinfunction "INA_1") (pintype "bidirectional"))
      (node (ref "IC4") (pin "4") (pinfunction "INB_4") (pintype "bidirectional"))
      (node (ref "J1") (pin "A4_B9") (pinfunction "VBUS_A4_B9") (pintype "power_in"))
      (node (ref "J1") (pin "B4_A9") (pinfunction "VBUS_B4_A9") (pintype "power_in"))
      (node (ref "L1") (pin "1") (pinfunction "1_1") (pintype "passive"))
      (node (ref "Q1") (pin "3") (pinfunction "D_3") (pintype "passive"))
      (node (ref "R3") (pin "1") (pinfunction "1_1") (pintype "passive"))
      (node (ref "R4") (pin "1") (pinfunction "1_1") (pintype "passive"))
    )
    (net (code "66") (name "unconnected-(IC1-ANT-Pad13)") (class "Default")
      (node (ref "IC1") (pin "13") (pinfunction "ANT_13") (pintype "bidirectional"))
    )
    (net (code "67") (name "unconnected-(IC1-GND_2-Pad12)") (class "Default")
      (node (ref "IC1") (pin "12") (pinfunction "GND_2_12") (pintype "bidirectional"))
    )
    (net (code "68") (name "unconnected-(IC1-GND_3-Pad14)") (class "Default")
      (node (ref "IC1") (pin "14") (pinfunction "GND_3_14") (pintype "bidirectional"))
    )
    (net (code "69") (name "unconnected-(IC1-GND_4-Pad26)") (class "Default")
      (node (ref "IC1") (pin "26") (pinfunction "GND_4_26") (pintype "bidirectional"))
    )
    (net (code "70") (name "unconnected-(IC1-GND_5-Pad30)") (class "Default")
      (node (ref "IC1") (pin "30") (pinfunction "GND_5_30") (pintype "bidirectional"))
    )
    (net (code "71") (name "unconnected-(IC1-GND_6-Pad53)") (class "Default")
      (node (ref "IC1") (pin "53") (pinfunction "GND_6_53") (pintype "bidirectional"))
    )
    (net (code "72") (name "unconnected-(IC1-GND_7-Pad56)") (class "Default")
      (node (ref "IC1") (pin "56") (pinfunction "GND_7_56") (pintype "bidirectional"))
    )
    (net (code "73") (name "unconnected-(IC1-GND_8-Pad57)") (class "Default")
      (node (ref "IC1") (pin "57") (pinfunction "GND_8_57") (pintype "bidirectional"))
    )
    (net (code "74") (name "unconnected-(IC1-GND_9-Pad58)") (class "Default")
      (node (ref "IC1") (pin "58") (pinfunction "GND_9_58") (pintype "bidirectional"))
    )
    (net (code "75") (name "unconnected-(IC1-GND_10-Pad59)") (class "Default")
      (node (ref "IC1") (pin "59") (pinfunction "GND_10_59") (pintype "bidirectional"))
    )
    (net (code "76") (name "unconnected-(IC1-GND_11-Pad60)") (class "Default")
      (node (ref "IC1") (pin "60") (pinfunction "GND_11_60") (pintype "bidirectional"))
    )
    (net (code "77") (name "unconnected-(IC1-GND_13-Pad62)") (class "Default")
      (node (ref "IC1") (pin "62") (pinfunction "GND_13_62") (pintype "bidirectional"))
    )
    (net (code "78") (name "unconnected-(IC1-GND_14-Pad63)") (class "Default")
      (node (ref "IC1") (pin "63") (pinfunction "GND_14_63") (pintype "bidirectional"))
    )
    (net (code "79") (name "unconnected-(IC1-GND_15-Pad64)") (class "Default")
      (node (ref "IC1") (pin "64") (pinfunction "GND_15_64") (pintype "bidirectional"))
    )
    (net (code "80") (name "unconnected-(IC1-GND_16-Pad65)") (class "Default")
      (node (ref "IC1") (pin "65") (pinfunction "GND_16_65") (pintype "bidirectional"))
    )
    (net (code "81") (name "unconnected-(IC1-GND_17-Pad66)") (class "Default")
      (node (ref "IC1") (pin "66") (pinfunction "GND_17_66") (pintype "bidirectional"))
    )
    (net (code "82") (name "unconnected-(IC1-GND_19-Pad68)") (class "Default")
      (node (ref "IC1") (pin "68") (pinfunction "GND_19_68") (pintype "bidirectional"))
    )
    (net (code "83") (name "unconnected-(IC1-GND_20-Pad69)") (class "Default")
      (node (ref "IC1") (pin "69") (pinfunction "GND_20_69") (pintype "bidirectional"))
    )
    (net (code "84") (name "unconnected-(IC1-GND_21-Pad70)") (class "Default")
      (node (ref "IC1") (pin "70") (pinfunction "GND_21_70") (pintype "bidirectional"))
    )
    (net (code "85") (name "unconnected-(IC1-GND_22-Pad71)") (class "Default")
      (node (ref "IC1") (pin "71") (pinfunction "GND_22_71") (pintype "bidirectional"))
    )
    (net (code "86") (name "unconnected-(IC1-GPIO_1-Pad1)") (class "Default")
      (node (ref "IC1") (pin "1") (pinfunction "GPIO_1_1") (pintype "bidirectional"))
    )
    (net (code "87") (name "unconnected-(IC1-GPIO_2-Pad2)") (class "Default")
      (node (ref "IC1") (pin "2") (pinfunction "GPIO_2_2") (pintype "bidirectional"))
    )
    (net (code "88") (name "unconnected-(IC1-GPIO_3-Pad3)") (class "Default")
      (node (ref "IC1") (pin "3") (pinfunction "GPIO_3_3") (pintype "bidirectional"))
    )
    (net (code "89") (name "unconnected-(IC1-GPIO_4-Pad4)") (class "Default")
      (node (ref "IC1") (pin "4") (pinfunction "GPIO_4_4") (pintype "bidirectional"))
    )
    (net (code "90") (name "unconnected-(IC1-GPIO_5-Pad5)") (class "Default")
      (node (ref "IC1") (pin "5") (pinfunction "GPIO_5_5") (pintype "bidirectional"))
    )
    (net (code "91") (name "unconnected-(IC1-GPIO_7-Pad7)") (class "Default")
      (node (ref "IC1") (pin "7") (pinfunction "GPIO_7_7") (pintype "bidirectional"))
    )
    (net (code "92") (name "unconnected-(IC1-GPIO_16-Pad16)") (class "Default")
      (node (ref "IC1") (pin "16") (pinfunction "GPIO_16_16") (pintype "bidirectional"))
    )
    (net (code "93") (name "unconnected-(IC1-GPIO_17-Pad17)") (class "Default")
      (node (ref "IC1") (pin "17") (pinfunction "GPIO_17_17") (pintype "bidirectional"))
    )
    (net (code "94") (name "unconnected-(IC1-GPIO_18-Pad18)") (class "Default")
      (node (ref "IC1") (pin "18") (pinfunction "GPIO_18_18") (pintype "bidirectional"))
    )
    (net (code "95") (name "unconnected-(IC1-GPIO_20-Pad20)") (class "Default")
      (node (ref "IC1") (pin "20") (pinfunction "GPIO_20_20") (pintype "bidirectional"))
    )
    (net (code "96") (name "unconnected-(IC1-GPIO_21-Pad21)") (class "Default")
      (node (ref "IC1") (pin "21") (pinfunction "GPIO_21_21") (pintype "bidirectional"))
    )
    (net (code "97") (name "unconnected-(IC1-GPIO_22-Pad22)") (class "Default")
      (node (ref "IC1") (pin "22") (pinfunction "GPIO_22_22") (pintype "bidirectional"))
    )
    (net (code "98") (name "unconnected-(IC1-GPIO_23-Pad23)") (class "Default")
      (node (ref "IC1") (pin "23") (pinfunction "GPIO_23_23") (pintype "bidirectional"))
    )
    (net (code "99") (name "unconnected-(IC1-GPIO_24-Pad24)") (class "Default")
      (node (ref "IC1") (pin "24") (pinfunction "GPIO_24_24") (pintype "bidirectional"))
    )
    (net (code "100") (name "unconnected-(IC1-GPIO_25-Pad25)") (class "Default")
      (node (ref "IC1") (pin "25") (pinfunction "GPIO_25_25") (pintype "bidirectional"))
    )
    (net (code "101") (name "unconnected-(IC1-GPIO_27-Pad27)") (class "Default")
      (node (ref "IC1") (pin "27") (pinfunction "GPIO_27_27") (pintype "bidirectional"))
    )
    (net (code "102") (name "unconnected-(IC1-GPIO_37-Pad37)") (class "Default")
      (node (ref "IC1") (pin "37") (pinfunction "GPIO_37_37") (pintype "bidirectional"))
    )
    (net (code "103") (name "unconnected-(IC1-GPIO_38-Pad38)") (class "Default")
      (node (ref "IC1") (pin "38") (pinfunction "GPIO_38_38") (pintype "bidirectional"))
    )
    (net (code "104") (name "unconnected-(IC1-GPIO_39-Pad39)") (class "Default")
      (node (ref "IC1") (pin "39") (pinfunction "GPIO_39_39") (pintype "bidirectional"))
    )
    (net (code "105") (name "unconnected-(IC1-GPIO_40-Pad40)") (class "Default")
      (node (ref "IC1") (pin "40") (pinfunction "GPIO_40_40") (pintype "bidirectional"))
    )
    (net (code "106") (name "unconnected-(IC1-GPIO_41-Pad41)") (class "Default")
      (node (ref "IC1") (pin "41") (pinfunction "GPIO_41_41") (pintype "bidirectional"))
    )
    (net (code "107") (name "unconnected-(IC1-GPIO_42-Pad42)") (class "Default")
      (node (ref "IC1") (pin "42") (pinfunction "GPIO_42_42") (pintype "bidirectional"))
    )
    (net (code "108") (name "unconnected-(IC1-GPIO_43-Pad43)") (class "Default")
      (node (ref "IC1") (pin "43") (pinfunction "GPIO_43_43") (pintype "bidirectional"))
    )
    (net (code "109") (name "unconnected-(IC1-GPIO_44-Pad44)") (class "Default")
      (node (ref "IC1") (pin "44") (pinfunction "GPIO_44_44") (pintype "bidirectional"))
    )
    (net (code "110") (name "unconnected-(IC1-NFC1{slash}GPIO_28-Pad28)") (class "Default")
      (node (ref "IC1") (pin "28") (pinfunction "NFC1/GPIO_28_28") (pintype "bidirectional"))
    )
    (net (code "111") (name "unconnected-(IC1-NFC2{slash}GPIO_29-Pad29)") (class "Default")
      (node (ref "IC1") (pin "29") (pinfunction "NFC2/GPIO_29_29") (pintype "bidirectional"))
    )
    (net (code "112") (name "unconnected-(IC1-QSPI_CLK{slash}GPIO_52-Pad52)") (class "Default")
      (node (ref "IC1") (pin "52") (pinfunction "QSPI_CLK/GPIO_52_52") (pintype "bidirectional"))
    )
    (net (code "113") (name "unconnected-(IC1-QSPI_CS{slash}GPIO_51-Pad51)") (class "Default")
      (node (ref "IC1") (pin "51") (pinfunction "QSPI_CS/GPIO_51_51") (pintype "bidirectional"))
    )
    (net (code "114") (name "unconnected-(IC1-QSPI_D0{slash}GPIO_50-Pad50)") (class "Default")
      (node (ref "IC1") (pin "50") (pinfunction "QSPI_D0/GPIO_50_50") (pintype "bidirectional"))
    )
    (net (code "115") (name "unconnected-(IC1-QSPI_D1{slash}GPIO_48-Pad48)") (class "Default")
      (node (ref "IC1") (pin "48") (pinfunction "QSPI_D1/GPIO_48_48") (pintype "bidirectional"))
    )
    (net (code "116") (name "unconnected-(IC1-QSPI_D2{slash}GPIO_49-Pad49)") (class "Default")
      (node (ref "IC1") (pin "49") (pinfunction "QSPI_D2/GPIO_49_49") (pintype "bidirectional"))
    )
    (net (code "117") (name "unconnected-(IC1-QSPI_D3{slash}GPIO_47-Pad47)") (class "Default")
      (node (ref "IC1") (pin "47") (pinfunction "QSPI_D3/GPIO_47_47") (pintype "bidirectional"))
    )
    (net (code "118") (name "unconnected-(IC1-RESET_N-Pad19)") (class "Default")
      (node (ref "IC1") (pin "19") (pinfunction "RESET_N_19") (pintype "bidirectional"))
    )
    (net (code "119") (name "unconnected-(IC1-SWDCLK-Pad11)") (class "Default")
      (node (ref "IC1") (pin "11") (pinfunction "SWDCLK_11") (pintype "bidirectional"))
    )
    (net (code "120") (name "unconnected-(IC1-SWDIO-Pad15)") (class "Default")
      (node (ref "IC1") (pin "15") (pinfunction "SWDIO_15") (pintype "bidirectional"))
    )
    (net (code "121") (name "unconnected-(IC1-SWO{slash}TRACE_D0{slash}_GPIO_8-Pad8)") (class "Default")
      (node (ref "IC1") (pin "8") (pinfunction "SWO/TRACE_D0/_GPIO_8_8") (pintype "bidirectional"))
    )
    (net (code "122") (name "unconnected-(IC1-TRACE_CLK{slash}GPIO_45-Pad45)") (class "Default")
      (node (ref "IC1") (pin "45") (pinfunction "TRACE_CLK/GPIO_45_45") (pintype "bidirectional"))
    )
    (net (code "123") (name "unconnected-(IC1-TRACE_D1{slash}GPIO_46-Pad46)") (class "Default")
      (node (ref "IC1") (pin "46") (pinfunction "TRACE_D1/GPIO_46_46") (pintype "bidirectional"))
    )
    (net (code "124") (name "unconnected-(IC1-USB_DM-Pad55)") (class "Default")
      (node (ref "IC1") (pin "55") (pinfunction "USB_DM_55") (pintype "bidirectional"))
    )
    (net (code "125") (name "unconnected-(IC1-USB_DP-Pad54)") (class "Default")
      (node (ref "IC1") (pin "54") (pinfunction "USB_DP_54") (pintype "bidirectional"))
    )
    (net (code "126") (name "unconnected-(IC1-VBUS-Pad31)") (class "Default")
      (node (ref "IC1") (pin "31") (pinfunction "VBUS_31") (pintype "bidirectional"))
    )
    (net (code "127") (name "unconnected-(IC1-VCC-Pad10)") (class "Default")
      (node (ref "IC1") (pin "10") (pinfunction "VCC_10") (pintype "bidirectional"))
    )
    (net (code "128") (name "unconnected-(IC1-VCC_IO-Pad9)") (class "Default")
      (node (ref "IC1") (pin "9") (pinfunction "VCC_IO_9") (pintype "bidirectional"))
    )
    (net (code "129") (name "unconnected-(J1-SBU1-PadA8)") (class "Default")
      (node (ref "J1") (pin "A8") (pinfunction "SBU1_A8") (pintype "bidirectional"))
    )
    (net (code "130") (name "unconnected-(J1-SBU2-PadB8)") (class "Default")
      (node (ref "J1") (pin "B8") (pinfunction "SBU2_B8") (pintype "bidirectional"))
    )
    (net (code "131") (name "unconnected-(J3-CD{slash}DAT3-Pad2)") (class "Default")
      (node (ref "J3") (pin "2") (pinfunction "CD/DAT3_2") (pintype "bidirectional"))
    )
    (net (code "132") (name "unconnected-(J3-CLK-Pad5)") (class "Default")
      (node (ref "J3") (pin "5") (pinfunction "CLK_5") (pintype "bidirectional"))
    )
    (net (code "133") (name "unconnected-(J3-CMD-Pad3)") (class "Default")
      (node (ref "J3") (pin "3") (pinfunction "CMD_3") (pintype "bidirectional"))
    )
    (net (code "134") (name "unconnected-(J3-DAT0-Pad7)") (class "Default")
      (node (ref "J3") (pin "7") (pinfunction "DAT0_7") (pintype "bidirectional"))
    )
    (net (code "135") (name "unconnected-(J3-DAT1-Pad8)") (class "Default")
      (node (ref "J3") (pin "8") (pinfunction "DAT1_8") (pintype "bidirectional"))
    )
    (net (code "136") (name "unconnected-(J3-DAT2-Pad1)") (class "Default")
      (node (ref "J3") (pin "1") (pinfunction "DAT2_1") (pintype "bidirectional"))
    )
    (net (code "137") (name "unconnected-(J3-Pad9)") (class "Default")
      (node (ref "J3") (pin "9") (pinfunction "9_9") (pintype "bidirectional"))
    )
    (net (code "138") (name "unconnected-(J3-Pad10)") (class "Default")
      (node (ref "J3") (pin "10") (pinfunction "10_10") (pintype "bidirectional"))
    )
    (net (code "139") (name "unconnected-(J3-Pad11)") (class "Default")
      (node (ref "J3") (pin "11") (pinfunction "11_11") (pintype "bidirectional"))
    )
    (net (code "140") (name "unconnected-(J3-Pad12)") (class "Default")
      (node (ref "J3") (pin "12") (pinfunction "12_12") (pintype "bidirectional"))
    )
    (net (code "141") (name "unconnected-(J3-Pad13)") (class "Default")
      (node (ref "J3") (pin "13") (pinfunction "13_13") (pintype "bidirectional"))
    )
    (net (code "142") (name "unconnected-(J3-VDD-Pad4)") (class "Default")
      (node (ref "J3") (pin "4") (pinfunction "VDD_4") (pintype "bidirectional"))
    )
    (net (code "143") (name "unconnected-(J3-VSS-Pad6)") (class "Default")
      (node (ref "J3") (pin "6") (pinfunction "VSS_6") (pintype "bidirectional"))
    )
    (net (code "144") (name "unconnected-(U1-N.C.-Pad3)") (class "Default")
      (node (ref "U1") (pin "3") (pinfunction "N.C._3") (pintype "no_connect"))
    )
    (net (code "145") (name "unconnected-(U2-N.C.-Pad3)") (class "Default")
      (node (ref "U2") (pin "3") (pinfunction "N.C._3") (pintype "no_connect"))
    )
    (net (code "146") (name "unconnected-(U2-S3-Pad6)") (class "Default")
      (node (ref "U2") (pin "6") (pinfunction "S3_6") (pintype "bidirectional"))
    )
    (net (code "147") (name "unconnected-(U2-S4-Pad7)") (class "Default")
      (node (ref "U2") (pin "7") (pinfunction "S4_7") (pintype "bidirectional"))
    )
    (net (code "148") (name "unconnected-(U2-S5-Pad12)") (class "Default")
      (node (ref "U2") (pin "12") (pinfunction "S5_12") (pintype "bidirectional"))
    )
    (net (code "149") (name "unconnected-(U2-S6-Pad11)") (class "Default")
      (node (ref "U2") (pin "11") (pinfunction "S6_11") (pintype "bidirectional"))
    )
    (net (code "150") (name "unconnected-(U2-S7-Pad10)") (class "Default")
      (node (ref "U2") (pin "10") (pinfunction "S7_10") (pintype "bidirectional"))
    )
    (net (code "151") (name "unconnected-(U2-S8-Pad9)") (class "Default")
      (node (ref "U2") (pin "9") (pinfunction "S8_9") (pintype "bidirectional"))
    )
    (net (code "152") (name "unconnected-(U3-N.C.-Pad3)") (class "Default")
      (node (ref "U3") (pin "3") (pinfunction "N.C._3") (pintype "no_connect"))
    )
    (net (code "153") (name "unconnected-(U4-N.C.-Pad3)") (class "Default")
      (node (ref "U4") (pin "3") (pinfunction "N.C._3") (pintype "no_connect"))
    )
    (net (code "154") (name "unconnected-(U4-S3-Pad6)") (class "Default")
      (node (ref "U4") (pin "6") (pinfunction "S3_6") (pintype "bidirectional"))
    )
    (net (code "155") (name "unconnected-(U4-S4-Pad7)") (class "Default")
      (node (ref "U4") (pin "7") (pinfunction "S4_7") (pintype "bidirectional"))
    )
    (net (code "156") (name "unconnected-(U4-S5-Pad12)") (class "Default")
      (node (ref "U4") (pin "12") (pinfunction "S5_12") (pintype "bidirectional"))
    )
    (net (code "157") (name "unconnected-(U4-S6-Pad11)") (class "Default")
      (node (ref "U4") (pin "11") (pinfunction "S6_11") (pintype "bidirectional"))
    )
    (net (code "158") (name "unconnected-(U4-S7-Pad10)") (class "Default")
      (node (ref "U4") (pin "10") (pinfunction "S7_10") (pintype "bidirectional"))
    )
    (net (code "159") (name "unconnected-(U4-S8-Pad9)") (class "Default")
      (node (ref "U4") (pin "9") (pinfunction "S8_9") (pintype "bidirectional"))
    )
  )
)
